# GNSS.net
KiCad netlist of a schematic drawn in Altium Designer
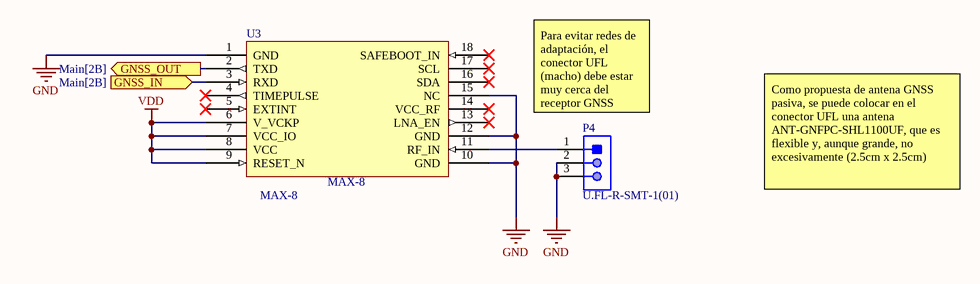
[diagram p0: GNSS.SchDoc]

(export (version "E")
  (design (tool "Eeschema 10.0.6"))
  (components
    (comp (ref "P4")
      (value "U.FL-R-SMT-1(01)")
      (footprint "HRS-U.FL-R-SMT-3_V")
      (description "Ultra Small Coaxial Connector, 6 GHz, -40 to 90 degC, 3-Pin SMD, RoHS, Bulk")
      (fields (field (name "MANUFACTURER") "Hirose Electric"))
      (libsource (lib "Altium Content Vault") (part "CN-1P-M-R3"))
    )
    (comp (ref "U3") (value "MAX-8") (footprint "MAX-8 LCC18") (libsource (lib "DEOP2425") (part "MAX-8")))
  )
  (nets
    (net (code "1") (name "/GNSS_IN") (class "Default")
      (node (ref "U3") (pin "3") (pinfunction "RXD_3") (pintype "input"))
    )
    (net (code "2") (name "/GNSS_OUT") (class "Default")
      (node (ref "U3") (pin "2") (pinfunction "TXD_2") (pintype "output"))
    )
    (net (code "3") (name "GND") (class "Default")
      (node (ref "P4") (pin "2") (pinfunction "2_2") (pintype "passive"))
      (node (ref "P4") (pin "3") (pinfunction "3_3") (pintype "passive"))
      (node (ref "U3") (pin "1") (pinfunction "GND_1") (pintype "power_in"))
      (node (ref "U3") (pin "10") (pinfunction "GND_10") (pintype "power_in"))
      (node (ref "U3") (pin "12") (pinfunction "GND_12") (pintype "power_in"))
      (node (ref "U3") (pin "15") (pinfunction "NC_15") (pintype "passive"))
    )
    (net (code "4") (name "Net-(U3-RF_IN)") (class "Default")
      (node (ref "P4") (pin "1") (pinfunction "1_1") (pintype "passive"))
      (node (ref "U3") (pin "11") (pinfunction "RF_IN_11") (pintype "input"))
    )
    (net (code "5") (name "VDD") (class "Default")
      (node (ref "U3") (pin "6") (pinfunction "V_VCKP_6") (pintype "power_in"))
      (node (ref "U3") (pin "7") (pinfunction "VCC_IO_7") (pintype "power_in"))
      (node (ref "U3") (pin "8") (pinfunction "VCC_8") (pintype "power_in"))
      (node (ref "U3") (pin "9") (pinfunction "RESET_N_9") (pintype "input"))
    )
    (net (code "6") (name "unconnected-(U3-EXTINT-Pad5)") (class "Default")
      (node (ref "U3") (pin "5") (pinfunction "EXTINT_5") (pintype "input+no_connect"))
    )
    (net (code "7") (name "unconnected-(U3-LNA_EN-Pad13)") (class "Default")
      (node (ref "U3") (pin "13") (pinfunction "LNA_EN_13") (pintype "output+no_connect"))
    )
    (net (code "8") (name "unconnected-(U3-SAFEBOOT_IN-Pad18)") (class "Default")
      (node (ref "U3") (pin "18") (pinfunction "SAFEBOOT_IN_18") (pintype "input+no_connect"))
    )
    (net (code "9") (name "unconnected-(U3-SCL-Pad17)") (class "Default")
      (node (ref "U3") (pin "17") (pinfunction "SCL_17") (pintype "tri_state+no_connect"))
    )
    (net (code "10") (name "unconnected-(U3-SDA-Pad16)") (class "Default")
      (node (ref "U3") (pin "16") (pinfunction "SDA_16") (pintype "tri_state+no_connect"))
    )
    (net (code "11") (name "unconnected-(U3-TIMEPULSE-Pad4)") (class "Default")
      (node (ref "U3") (pin "4") (pinfunction "TIMEPULSE_4") (pintype "output+no_connect"))
    )
    (net (code "12") (name "unconnected-(U3-VCC_RF-Pad14)") (class "Default")
      (node (ref "U3") (pin "14") (pinfunction "VCC_RF_14") (pintype "power_in+no_connect"))
    )
  )
)
